# RFID.net
KiCad netlist of a schematic drawn in Altium Designer
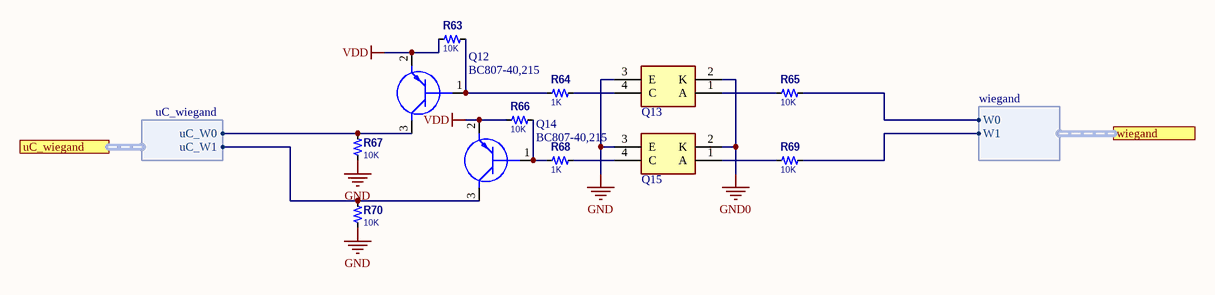
[diagram p0: RFID.SchDoc]

(export (version "E")
  (design (tool "Eeschema 10.0.6"))
  (components
    (comp (ref "Q12")
      (value "BC807-40,215")
      (footprint "SamacSys:SOT95P230X110-3N")
      (description "Transistor BJT PNP")
      (fields (field (name "MOUSER PART NUMBER") "771-BC807-40-T/R"))
      (libsource (lib "*") (part "BC807-40,215"))
    )
    (comp (ref "Q13")
      (value "TLX9291A_GBTPL,F")
      (footprint "SamacSys:SOIC127P700X230-4N")
      (description "Phototransistor")
      (fields
        (field (name "MANUFACTURER_PART_NUMBER") "TLX9291A(GBTPL,F")
        (field (name "MOUSER PART NUMBER") "757-TLX9291AGBTPLF")
      )
      (libsource (lib "*") (part "TLX9291A_GBTPL,F"))
    )
    (comp (ref "Q14")
      (value "BC807-40,215")
      (footprint "SamacSys:SOT95P230X110-3N")
      (description "Transistor BJT PNP")
      (fields (field (name "MOUSER PART NUMBER") "771-BC807-40-T/R"))
      (libsource (lib "*") (part "BC807-40,215"))
    )
    (comp (ref "Q15")
      (value "TLX9291A_GBTPL,F")
      (footprint "SamacSys:SOIC127P700X230-4N")
      (description "Phototransistor")
      (fields
        (field (name "MANUFACTURER_PART_NUMBER") "TLX9291A(GBTPL,F")
        (field (name "MOUSER PART NUMBER") "757-TLX9291AGBTPLF")
      )
      (libsource (lib "*") (part "TLX9291A_GBTPL,F"))
    )
    (comp (ref "R63")
      (value "10K")
      (footprint "0603-R")
      (fields
        (field (name "MANUFACTURER") "Panasonic")
        (field (name "MANUFACTURER PART NUMBER") "ERJ-8GEYJ621V")
        (field (name "TOLERANCE") "5%")
      )
      (libsource (lib "ESP32_IO_module") (part "Res_2"))
    )
    (comp (ref "R64")
      (value "1K")
      (footprint "0603-R")
      (fields
        (field (name "MANUFACTURER") "Panasonic")
        (field (name "MANUFACTURER PART NUMBER") "ERJ-8GEYJ621V")
        (field (name "TOLERANCE") "5%")
      )
      (libsource (lib "ESP32_IO_module") (part "Res_2"))
    )
    (comp (ref "R65")
      (value "10K")
      (footprint "0603-R")
      (fields
        (field (name "MANUFACTURER") "Panasonic")
        (field (name "MANUFACTURER PART NUMBER") "ERJ-8GEYJ621V")
        (field (name "TOLERANCE") "5%")
      )
      (libsource (lib "ESP32_IO_module") (part "Res_2"))
    )
    (comp (ref "R66")
      (value "10K")
      (footprint "0603-R")
      (fields
        (field (name "MANUFACTURER") "Panasonic")
        (field (name "MANUFACTURER PART NUMBER") "ERJ-8GEYJ621V")
        (field (name "TOLERANCE") "5%")
      )
      (libsource (lib "ESP32_IO_module") (part "Res_2"))
    )
    (comp (ref "R67")
      (value "10K")
      (footprint "0603-R")
      (fields
        (field (name "MANUFACTURER") "Panasonic")
        (field (name "MANUFACTURER PART NUMBER") "ERJ-8GEYJ621V")
        (field (name "TOLERANCE") "5%")
      )
      (libsource (lib "ESP32_IO_module") (part "Res_2"))
    )
    (comp (ref "R68")
      (value "1K")
      (footprint "0603-R")
      (fields
        (field (name "MANUFACTURER") "Panasonic")
        (field (name "MANUFACTURER PART NUMBER") "ERJ-8GEYJ621V")
        (field (name "TOLERANCE") "5%")
      )
      (libsource (lib "ESP32_IO_module") (part "Res_2"))
    )
    (comp (ref "R69")
      (value "10K")
      (footprint "0603-R")
      (fields
        (field (name "MANUFACTURER") "Panasonic")
        (field (name "MANUFACTURER PART NUMBER") "ERJ-8GEYJ621V")
        (field (name "TOLERANCE") "5%")
      )
      (libsource (lib "ESP32_IO_module") (part "Res_2"))
    )
    (comp (ref "R70")
      (value "10K")
      (footprint "0603-R")
      (fields
        (field (name "MANUFACTURER") "Panasonic")
        (field (name "MANUFACTURER PART NUMBER") "ERJ-8GEYJ621V")
        (field (name "TOLERANCE") "5%")
      )
      (libsource (lib "ESP32_IO_module") (part "Res_2"))
    )
  )
  (nets
    (net (code "3") (name "/W0") (class "Default")
      (node (ref "R65") (pin "1") (pinfunction "1_1") (pintype "passive"))
    )
    (net (code "4") (name "/W1") (class "Default")
      (node (ref "R69") (pin "1") (pinfunction "1_1") (pintype "passive"))
    )
    (net (code "5") (name "/uC_W0") (class "Default")
      (node (ref "Q12") (pin "3") (pinfunction "C_3") (pintype "passive"))
      (node (ref "R67") (pin "1") (pinfunction "1_1") (pintype "passive"))
    )
    (net (code "6") (name "/uC_W1") (class "Default")
      (node (ref "Q14") (pin "3") (pinfunction "C_3") (pintype "passive"))
      (node (ref "R70") (pin "1") (pinfunction "1_1") (pintype "passive"))
    )
    (net (code "9") (name "GND") (class "Default")
      (node (ref "Q13") (pin "3") (pinfunction "E_3") (pintype "passive"))
      (node (ref "Q15") (pin "3") (pinfunction "E_3") (pintype "passive"))
      (node (ref "R67") (pin "2") (pinfunction "2_2") (pintype "passive"))
      (node (ref "R70") (pin "2") (pinfunction "2_2") (pintype "passive"))
    )
    (net (code "10") (name "GND0") (class "Default")
      (node (ref "Q13") (pin "2") (pinfunction "K_2") (pintype "passive"))
      (node (ref "Q15") (pin "2") (pinfunction "K_2") (pintype "passive"))
    )
    (net (code "11") (name "Net-(Q12-B)") (class "Default")
      (node (ref "Q12") (pin "1") (pinfunction "B_1") (pintype "passive"))
      (node (ref "R63") (pin "1") (pinfunction "1_1") (pintype "passive"))
      (node (ref "R64") (pin "2") (pinfunction "2_2") (pintype "passive"))
    )
    (net (code "12") (name "Net-(Q13-A)") (class "Default")
      (node (ref "Q13") (pin "1") (pinfunction "A_1") (pintype "passive"))
      (node (ref "R65") (pin "2") (pinfunction "2_2") (pintype "passive"))
    )
    (net (code "13") (name "Net-(Q13-C)") (class "Default")
      (node (ref "Q13") (pin "4") (pinfunction "C_4") (pintype "passive"))
      (node (ref "R64") (pin "1") (pinfunction "1_1") (pintype "passive"))
    )
    (net (code "14") (name "Net-(Q14-B)") (class "Default")
      (node (ref "Q14") (pin "1") (pinfunction "B_1") (pintype "passive"))
      (node (ref "R66") (pin "1") (pinfunction "1_1") (pintype "passive"))
      (node (ref "R68") (pin "2") (pinfunction "2_2") (pintype "passive"))
    )
    (net (code "15") (name "Net-(Q15-A)") (class "Default")
      (node (ref "Q15") (pin "1") (pinfunction "A_1") (pintype "passive"))
      (node (ref "R69") (pin "2") (pinfunction "2_2") (pintype "passive"))
    )
    (net (code "16") (name "Net-(Q15-C)") (class "Default")
      (node (ref "Q15") (pin "4") (pinfunction "C_4") (pintype "passive"))
      (node (ref "R68") (pin "1") (pinfunction "1_1") (pintype "passive"))
    )
    (net (code "17") (name "VDD") (class "Default")
      (node (ref "Q12") (pin "2") (pinfunction "E_2") (pintype "passive"))
      (node (ref "Q14") (pin "2") (pinfunction "E_2") (pintype "passive"))
      (node (ref "R63") (pin "2") (pinfunction "2_2") (pintype "passive"))
      (node (ref "R66") (pin "2") (pinfunction "2_2") (pintype "passive"))
    )
  )
)
